# Power.net
KiCad netlist of a schematic drawn in Altium Designer
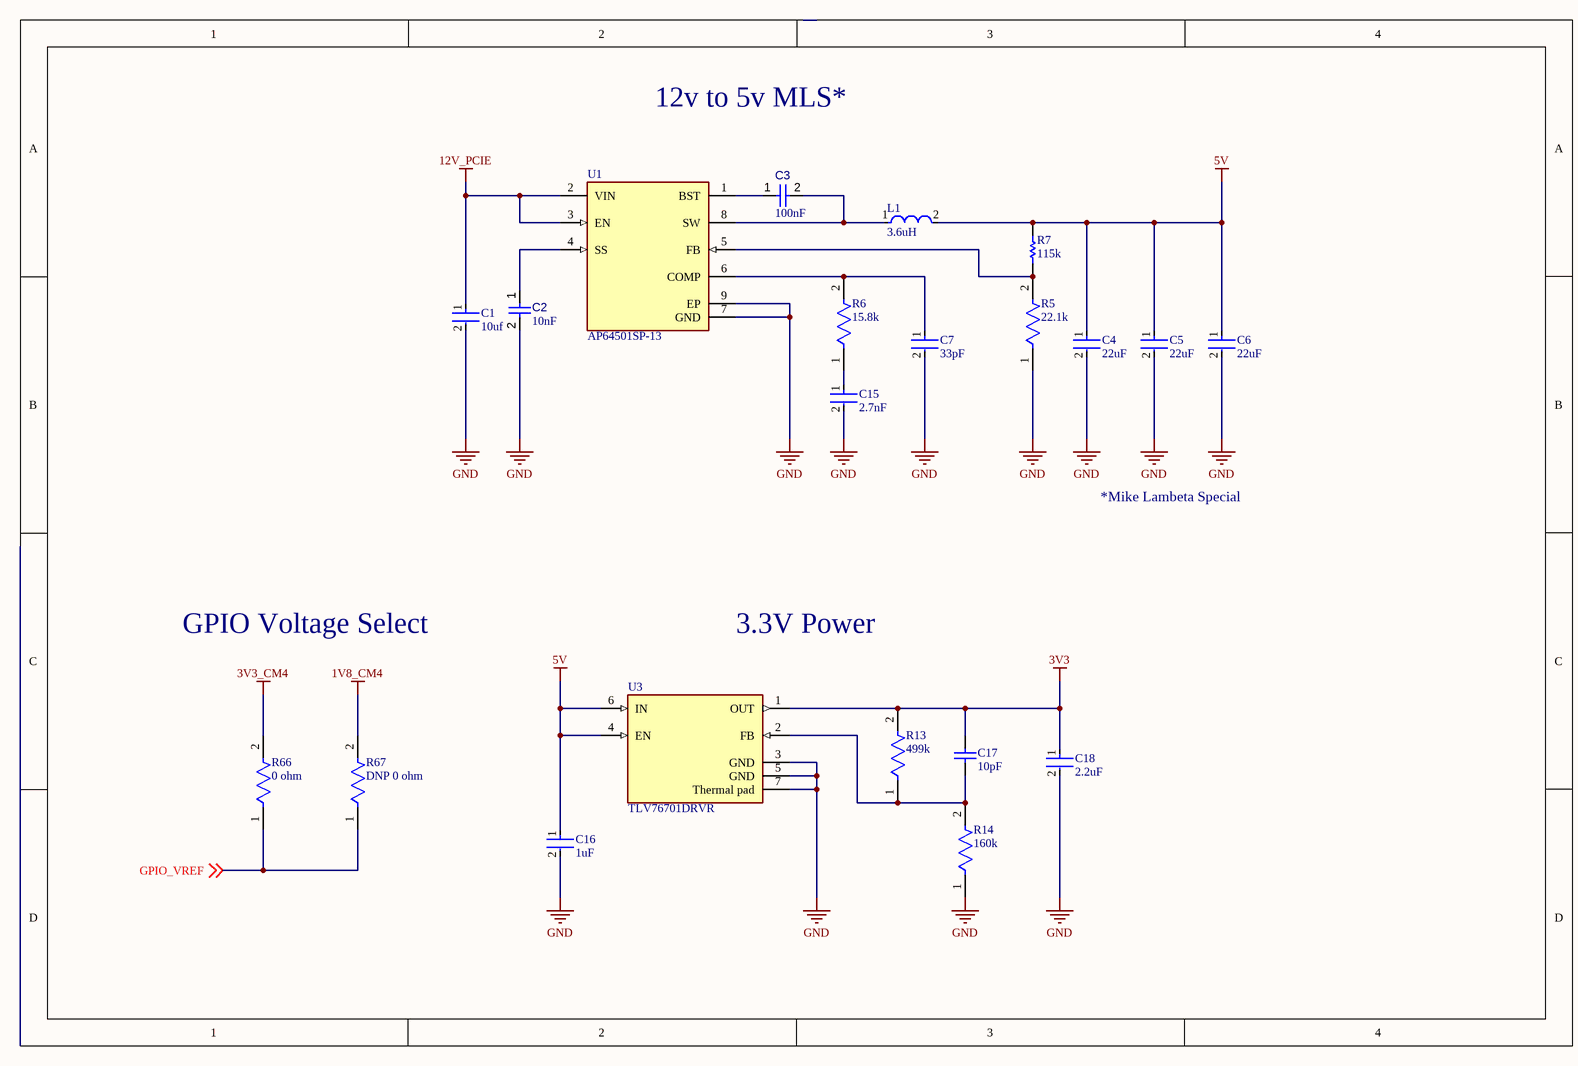
[diagram p0: Power.SchDoc]

(export (version "E")
  (design (tool "Eeschema 10.0.6"))
  (components
    (comp (ref "C1")
      (value "10uf")
      (footprint "FP-GRM188-0_2-IPC_C")
      (description "Chip Multilayer Ceramic Capacitors for General Purpose, 0603, 10uF, X5R, 15%, 20%, 35V")
      (fields (field (name "TOLERANCE") "20%"))
      (libsource (lib "Altium Content Vault") (part "11868f565c42a9108669ba33697ecf6"))
    )
    (comp (ref "C2")
      (value "10nF")
      (footprint "CAPC0402(1005)60_L")
      (description "Chip Capacitor, 10nF +/-20%, 50V, 0402, Thickness 0.6 mm")
      (fields (field (name "TOLERANCE") "5%") (field (name "Comment") "Capacitor 10nF +/-20% 50V 0402"))
      (libsource (lib "Lasse Johnsen") (part "CAP-NP-2"))
    )
    (comp (ref "C3")
      (value "100nF")
      (footprint "CAPC0402(1005)60_L")
      (description "Chip Capacitor, 100nF +/-20%, 25V, 0402, Thickness 0.6 mm")
      (fields (field (name "TOLERANCE") "10%") (field (name "Comment") "Capacitor 100nF +/-20% 25V 0402"))
      (libsource (lib "Lasse Johnsen") (part "CAP-NP-2"))
    )
    (comp (ref "C4")
      (value "22uF")
      (footprint "FP-GRM21B-0_15-MFG")
      (description "Chip Multilayer Ceramic Capacitors for General Purpose, 0805, 22uF, X5R, 15%, 20%, 6.3V")
      (fields (field (name "VOLTAGE") "6.3V") (field (name "TOLERANCE") "20%"))
      (libsource (lib "Altium Content Vault") (part "b4654b650e69147ec39a6b967a45e02"))
    )
    (comp (ref "C5")
      (value "22uF")
      (footprint "FP-GRM21B-0_15-MFG")
      (description "Chip Multilayer Ceramic Capacitors for General Purpose, 0805, 22uF, X5R, 15%, 20%, 6.3V")
      (fields (field (name "VOLTAGE") "6.3V") (field (name "TOLERANCE") "20%"))
      (libsource (lib "Altium Content Vault") (part "b4654b650e69147ec39a6b967a45e02"))
    )
    (comp (ref "C6")
      (value "22uF")
      (footprint "FP-GRM21B-0_15-MFG")
      (description "Chip Multilayer Ceramic Capacitors for General Purpose, 0805, 22uF, X5R, 15%, 20%, 6.3V")
      (fields (field (name "VOLTAGE") "6.3V") (field (name "TOLERANCE") "20%"))
      (libsource (lib "Altium Content Vault") (part "b4654b650e69147ec39a6b967a45e02"))
    )
    (comp (ref "C7")
      (value "33pF")
      (footprint "FP-0402-L_1_0_1-W_0_5_0_1-IPC_A")
      (description "General Purpose Ceramic Capacitor, 0402, 33pF, 5%, C0G, 30ppm/°C, 50V")
      (fields (field (name "TOLERANCE") "5%") (field (name "VOLTAGE") "50V"))
      (libsource (lib "Altium Content Vault") (part "b4654b650e69147ec39a6b967a45e02"))
    )
    (comp (ref "C15")
      (value "2.7nF")
      (footprint "FP-CL10-IPC_C")
      (description "Cap Ceramic 2.7nF 50V X7R ±10% Pad SMD 0603 +125°C T/R")
      (fields (field (name "TOLERANCE") "10%") (field (name "VOLTAGE") "50V"))
      (libsource (lib "Altium Content Vault") (part "b4654b650e69147ec39a6b967a45e02"))
    )
    (comp (ref "C16")
      (value "1uF")
      (footprint "FP-CC0805-0_85-MFG")
      (description "CAP CER 1UF 10V X7R 0805")
      (fields
        (field (name "MANUFACTURER") "Yageo")
        (field (name "OCTOPART") "https://octopart.com/cc0805kkx7r6bb105-yageo-42522859")
      )
      (libsource (lib "Altium Content Vault") (part "11868f565c42a9108669ba33697ecf6"))
    )
    (comp (ref "C17")
      (value "10pF")
      (footprint "CAPC1005X55X25ML05T05")
      (description "Chip Capacitor, 10 pF, +/- 5%, 50 V, -55 to 125 degC, 0402 (1005 Metric), RoHS, Tape and Reel")
      (fields (field (name "TOLERANCE") "5%") (field (name "MANUFACTURER") "Yageo"))
      (libsource (lib "Altium Content Vault") (part "CAP-NP-2"))
    )
    (comp (ref "C18")
      (value "2.2uF")
      (footprint "FP-CC0603-DA-MFG")
      (description "CAP CER 2.2UF 10V X5R 0603")
      (fields (field (name "TOLERANCE") "0.1") (field (name "MANUFACTURER") "YAGEO"))
      (libsource (lib "Altium Content Vault") (part "11868f565c42a9108669ba33697ecf6"))
    )
    (comp (ref "L1")
      (value "3.6uH")
      (footprint "FP-NR8040-H_4_2-MFG")
      (description "Shielded Wirewound Inductor 3.6uH 30% 6A 19.5mΩ SMD Automotive")
      (fields (field (name "TOLERANCE") "30%"))
      (libsource (lib "Altium Content Vault") (part "725321dda6339637d4d059423bc1c3c"))
    )
    (comp (ref "R5")
      (value "22.1k")
      (footprint "FP-CRCW0402-e3-IPC_A")
      (description "RES Thick Film, 22.1kΩ, 1%, 0.063W, 100ppm/°C, 0402")
      (fields (field (name "TOLERANCE") "1%"))
      (libsource (lib "Altium Content Vault") (part "1029c3af85768c4190bb7ad29bc67b5"))
    )
    (comp (ref "R6")
      (value "15.8k")
      (footprint "FP-CRCW0402-e3-IPC_C")
      (description "RES Thick Film, 15.8kΩ, 1%, 0.063W, 100ppm/°C, 0402")
      (fields (field (name "TOLERANCE") "1%"))
      (libsource (lib "Altium Content Vault") (part "1029c3af85768c4190bb7ad29bc67b5"))
    )
    (comp (ref "R7")
      (value "115k")
      (footprint "RESC1005X40X25ML05T05")
      (fields (field (name "MANUFACTURER") "Panasonic") (field (name "PART NUMBER") "ERJ-2RKF1153X"))
      (libsource (lib "Altium Content Vault") (part "RES"))
    )
    (comp (ref "R13")
      (value "499k")
      (footprint "FP-CRCW0805-e3-MFG")
      (description "RES Thick Film, 499kΩ, 1%, 0.125W, 100ppm/°C, 0805")
      (fields (field (name "TOLERANCE") "1%"))
      (libsource (lib "Altium Content Vault") (part "1029c3af85768c4190bb7ad29bc67b5"))
    )
    (comp (ref "R14")
      (value "160k")
      (footprint "FP-CRCW0805-e3-IPC_C")
      (description "RES Thick Film, 160kΩ, 1%, 0.125W, 100ppm/°C, 0805")
      (fields (field (name "TOLERANCE") "1%"))
      (libsource (lib "Altium Content Vault") (part "1029c3af85768c4190bb7ad29bc67b5"))
    )
    (comp (ref "R66")
      (value "0 ohm")
      (footprint "FP-CRCW0603-HPe3-MFG")
      (description "RES Thick Film, 0Ω, , 0.33W, , 0603")
      (libsource (lib "Altium Content Vault") (part "1029c3af85768c4190bb7ad29bc67b5"))
    )
    (comp (ref "R67")
      (value "DNP 0 ohm")
      (footprint "FP-CRCW0603-HPe3-MFG")
      (description "RES Thick Film, 0Ω, , 0.33W, , 0603")
      (libsource (lib "Altium Content Vault") (part "1029c3af85768c4190bb7ad29bc67b5"))
    )
    (comp (ref "U1")
      (value "AP64501SP-13")
      (footprint "FP-SO-8EP-IPC_A")
      (description "DCDC CONV HV BUCK SO-8EP")
      (libsource (lib "Altium Content Vault") (part "5ebf8146ffb11b38024cfc6b6736e1a"))
    )
    (comp (ref "U3")
      (value "TLV76701DRVR")
      (footprint "FP-DRV0006A-IPC_C")
      (description "IC REG LINEAR POS ADJ 1A 6WSON")
      (libsource (lib "Altium Content Vault") (part "02b25d0a349586096ecc9dc1ae98da2"))
    )
  )
  (nets
    (net (code "1") (name "1V8_CM4") (class "Default")
      (node (ref "R67") (pin "2") (pinfunction "2_2") (pintype "passive"))
    )
    (net (code "2") (name "3V3") (class "Default")
      (node (ref "C17") (pin "2") (pinfunction "2_2") (pintype "passive"))
      (node (ref "C18") (pin "1") (pinfunction "1_1") (pintype "passive"))
      (node (ref "R13") (pin "2") (pinfunction "2_2") (pintype "passive"))
      (node (ref "U3") (pin "1") (pinfunction "OUT_1") (pintype "output"))
    )
    (net (code "3") (name "3V3_CM4") (class "Default")
      (node (ref "R66") (pin "2") (pinfunction "2_2") (pintype "passive"))
    )
    (net (code "4") (name "5V") (class "Default")
      (node (ref "C16") (pin "1") (pinfunction "1_1") (pintype "passive"))
      (node (ref "C4") (pin "1") (pinfunction "1_1") (pintype "passive"))
      (node (ref "C5") (pin "1") (pinfunction "1_1") (pintype "passive"))
      (node (ref "C6") (pin "1") (pinfunction "1_1") (pintype "passive"))
      (node (ref "L1") (pin "2") (pinfunction "2_2") (pintype "passive"))
      (node (ref "R7") (pin "2") (pinfunction "2_2") (pintype "passive"))
      (node (ref "U3") (pin "4") (pinfunction "EN_4") (pintype "input"))
      (node (ref "U3") (pin "6") (pinfunction "IN_6") (pintype "input"))
    )
    (net (code "5") (name "12V_PCIE") (class "Default")
      (node (ref "C1") (pin "1") (pinfunction "1_1") (pintype "passive"))
      (node (ref "U1") (pin "2") (pinfunction "VIN_2") (pintype "power_in"))
      (node (ref "U1") (pin "3") (pinfunction "EN_3") (pintype "input"))
    )
    (net (code "6") (name "GND") (class "Default")
      (node (ref "C1") (pin "2") (pinfunction "2_2") (pintype "passive"))
      (node (ref "C15") (pin "2") (pinfunction "2_2") (pintype "passive"))
      (node (ref "C16") (pin "2") (pinfunction "2_2") (pintype "passive"))
      (node (ref "C18") (pin "2") (pinfunction "2_2") (pintype "passive"))
      (node (ref "C2") (pin "2") (pinfunction "2_2") (pintype "passive"))
      (node (ref "C4") (pin "2") (pinfunction "2_2") (pintype "passive"))
      (node (ref "C5") (pin "2") (pinfunction "2_2") (pintype "passive"))
      (node (ref "C6") (pin "2") (pinfunction "2_2") (pintype "passive"))
      (node (ref "C7") (pin "2") (pinfunction "2_2") (pintype "passive"))
      (node (ref "R14") (pin "1") (pinfunction "1_1") (pintype "passive"))
      (node (ref "R5") (pin "1") (pinfunction "1_1") (pintype "passive"))
      (node (ref "U1") (pin "7") (pinfunction "GND_7") (pintype "power_in"))
      (node (ref "U1") (pin "9") (pinfunction "EP_9") (pintype "passive"))
      (node (ref "U3") (pin "3") (pinfunction "GND_3") (pintype "power_in"))
      (node (ref "U3") (pin "5") (pinfunction "GND_5") (pintype "power_in"))
      (node (ref "U3") (pin "7") (pinfunction "Thermal_pad_7") (pintype "power_in"))
    )
    (net (code "7") (name "GPIO_VREF") (class "Default")
      (node (ref "R66") (pin "1") (pinfunction "1_1") (pintype "passive"))
      (node (ref "R67") (pin "1") (pinfunction "1_1") (pintype "passive"))
    )
    (net (code "8") (name "Net-(C15-Pad1)") (class "Default")
      (node (ref "C15") (pin "1") (pinfunction "1_1") (pintype "passive"))
      (node (ref "R6") (pin "1") (pinfunction "1_1") (pintype "passive"))
    )
    (net (code "9") (name "Net-(U1-BST)") (class "Default")
      (node (ref "C3") (pin "1") (pinfunction "1_1") (pintype "passive"))
      (node (ref "U1") (pin "1") (pinfunction "BST_1") (pintype "passive"))
    )
    (net (code "10") (name "Net-(U1-COMP)") (class "Default")
      (node (ref "C7") (pin "1") (pinfunction "1_1") (pintype "passive"))
      (node (ref "R6") (pin "2") (pinfunction "2_2") (pintype "passive"))
      (node (ref "U1") (pin "6") (pinfunction "COMP_6") (pintype "passive"))
    )
    (net (code "11") (name "Net-(U1-FB)") (class "Default")
      (node (ref "R5") (pin "2") (pinfunction "2_2") (pintype "passive"))
      (node (ref "R7") (pin "1") (pinfunction "1_1") (pintype "passive"))
      (node (ref "U1") (pin "5") (pinfunction "FB_5") (pintype "input"))
    )
    (net (code "12") (name "Net-(U1-SS)") (class "Default")
      (node (ref "C2") (pin "1") (pinfunction "1_1") (pintype "passive"))
      (node (ref "U1") (pin "4") (pinfunction "SS_4") (pintype "input"))
    )
    (net (code "13") (name "Net-(U1-SW)") (class "Default")
      (node (ref "C3") (pin "2") (pinfunction "2_2") (pintype "passive"))
      (node (ref "L1") (pin "1") (pinfunction "1_1") (pintype "passive"))
      (node (ref "U1") (pin "8") (pinfunction "SW_8") (pintype "passive"))
    )
    (net (code "14") (name "Net-(U3-FB)") (class "Default")
      (node (ref "C17") (pin "1") (pinfunction "1_1") (pintype "passive"))
      (node (ref "R13") (pin "1") (pinfunction "1_1") (pintype "passive"))
      (node (ref "R14") (pin "2") (pinfunction "2_2") (pintype "passive"))
      (node (ref "U3") (pin "2") (pinfunction "FB_2") (pintype "input"))
    )
  )
)
